# Board.net
KiCad netlist of a schematic drawn in EAGLE
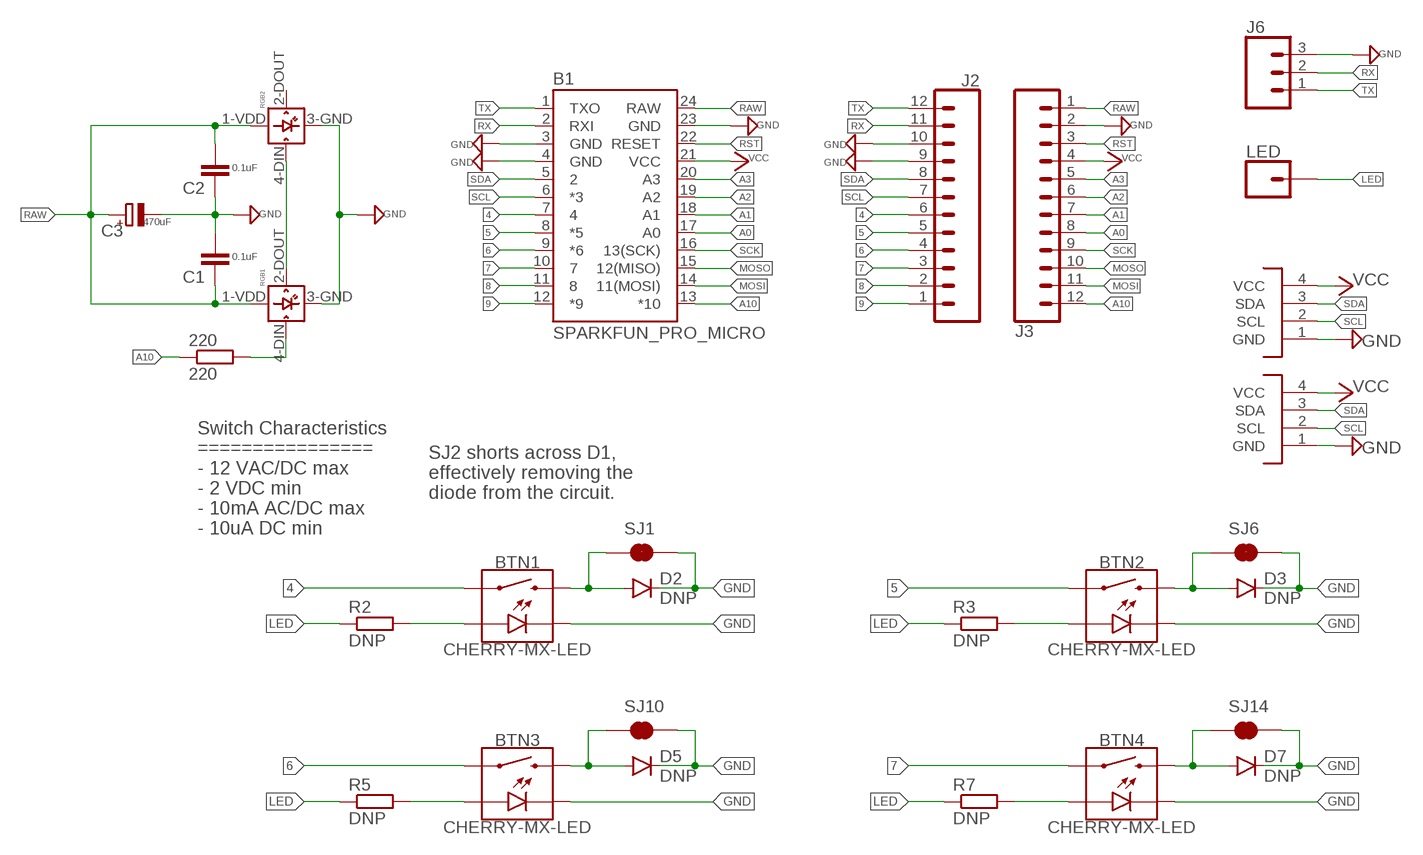
[diagram p0: schematic, sheet 1]

(export (version "E")
  (design (tool "Eeschema 10.0.6"))
  (components
    (comp (ref "220")
      (value "220")
      (footprint "eagle-import:0207_10")
      (libsource (lib "eagle-import") (part "resistor_348_R-EU_0207/10"))
    )
    (comp (ref "B1")
      (value "SPARKFUN_PRO_MICRO")
      (footprint "eagle-import:SPARKFUN_PRO_MICRO")
      (libsource (lib "eagle-import") (part "SPARKFUN_PRO_MICRO"))
    )
    (comp (ref "BTN1")
      (value "CHERRY-MX-LED")
      (footprint "eagle-import:CHERRY-MX-LED")
      (libsource (lib "eagle-import") (part "CHERRY-MX-LED"))
    )
    (comp (ref "BTN2")
      (value "CHERRY-MX-LED")
      (footprint "eagle-import:CHERRY-MX-LED")
      (libsource (lib "eagle-import") (part "CHERRY-MX-LED"))
    )
    (comp (ref "BTN3")
      (value "CHERRY-MX-LED")
      (footprint "eagle-import:CHERRY-MX-LED")
      (libsource (lib "eagle-import") (part "CHERRY-MX-LED"))
    )
    (comp (ref "BTN4")
      (value "CHERRY-MX-LED")
      (footprint "eagle-import:CHERRY-MX-LED")
      (libsource (lib "eagle-import") (part "CHERRY-MX-LED"))
    )
    (comp (ref "C1")
      (value "0.1uF")
      (footprint "eagle-import:CAP-PTH-SMALL-KIT")
      (libsource (lib "eagle-import") (part "0.1UF-KIT-EZ-50V-20%"))
    )
    (comp (ref "C2")
      (value "0.1uF")
      (footprint "eagle-import:CAP-PTH-SMALL-KIT")
      (libsource (lib "eagle-import") (part "0.1UF-KIT-EZ-50V-20%"))
    )
    (comp (ref "C3")
      (value "470uF")
      (footprint "eagle-import:E3,5-8")
      (libsource (lib "eagle-import") (part "CPOL-EUE3.5-8"))
    )
    (comp (ref "D2")
      (value "DNP")
      (footprint "eagle-import:DIODE-PTH-0.1")
      (libsource (lib "eagle-import") (part "DIODEPTH-VERT-0.1"))
    )
    (comp (ref "D3")
      (value "DNP")
      (footprint "eagle-import:DIODE-PTH-0.1")
      (libsource (lib "eagle-import") (part "DIODEPTH-VERT-0.1"))
    )
    (comp (ref "D5")
      (value "DNP")
      (footprint "eagle-import:DIODE-PTH-0.1")
      (libsource (lib "eagle-import") (part "DIODEPTH-VERT-0.1"))
    )
    (comp (ref "D7")
      (value "DNP")
      (footprint "eagle-import:DIODE-PTH-0.1")
      (libsource (lib "eagle-import") (part "DIODEPTH-VERT-0.1"))
    )
    (comp (ref "J2")
      (value "CONN_12")
      (footprint "eagle-import:1X12")
      (libsource (lib "eagle-import") (part "CONN_12"))
    )
    (comp (ref "J3")
      (value "CONN_12")
      (footprint "eagle-import:1X12")
      (libsource (lib "eagle-import") (part "CONN_12"))
    )
    (comp (ref "J4")
      (value "I2C-HEADER")
      (footprint "eagle-import:HEADER-4X1-2.54")
      (libsource (lib "eagle-import") (part "I2C-HEADER"))
    )
    (comp (ref "J5")
      (value "I2C-HEADER")
      (footprint "eagle-import:HEADER-4X1-2.54")
      (libsource (lib "eagle-import") (part "I2C-HEADER"))
    )
    (comp (ref "J6")
      (value "CONN_03")
      (footprint "eagle-import:1X03")
      (libsource (lib "eagle-import") (part "CONN_03"))
    )
    (comp (ref "LED")
      (value "CONN_01")
      (footprint "eagle-import:1X01")
      (libsource (lib "eagle-import") (part "CONN_01"))
    )
    (comp (ref "R2")
      (value "DNP")
      (footprint "eagle-import:0207_10")
      (libsource (lib "eagle-import") (part "R-EU_0207/10"))
    )
    (comp (ref "R3")
      (value "DNP")
      (footprint "eagle-import:0207_10")
      (libsource (lib "eagle-import") (part "R-EU_0207/10"))
    )
    (comp (ref "R5")
      (value "DNP")
      (footprint "eagle-import:0207_10")
      (libsource (lib "eagle-import") (part "R-EU_0207/10"))
    )
    (comp (ref "R7")
      (value "DNP")
      (footprint "eagle-import:0207_10")
      (libsource (lib "eagle-import") (part "R-EU_0207/10"))
    )
    (comp (ref "RGB1")
      (value "WS2812B")
      (footprint "eagle-import:WS2812B")
      (libsource (lib "eagle-import") (part "WS2812B"))
    )
    (comp (ref "RGB2")
      (value "WS2812B")
      (footprint "eagle-import:WS2812B")
      (libsource (lib "eagle-import") (part "WS2812B"))
    )
    (comp (ref "SJ1")
      (value "JUMPER-PAD-2-NC_BY_TRACENO_SILK")
      (footprint "eagle-import:PAD-JUMPER-2-NC_BY_TRACE_NO_SILK")
      (libsource (lib "eagle-import") (part "JUMPER-PAD-2-NC_BY_TRACENO_SILK"))
    )
    (comp (ref "SJ6")
      (value "JUMPER-PAD-2-NC_BY_TRACENO_SILK")
      (footprint "eagle-import:PAD-JUMPER-2-NC_BY_TRACE_NO_SILK")
      (libsource (lib "eagle-import") (part "JUMPER-PAD-2-NC_BY_TRACENO_SILK"))
    )
    (comp (ref "SJ10")
      (value "JUMPER-PAD-2-NC_BY_TRACENO_SILK")
      (footprint "eagle-import:PAD-JUMPER-2-NC_BY_TRACE_NO_SILK")
      (libsource (lib "eagle-import") (part "JUMPER-PAD-2-NC_BY_TRACENO_SILK"))
    )
    (comp (ref "SJ14")
      (value "JUMPER-PAD-2-NC_BY_TRACENO_SILK")
      (footprint "eagle-import:PAD-JUMPER-2-NC_BY_TRACE_NO_SILK")
      (libsource (lib "eagle-import") (part "JUMPER-PAD-2-NC_BY_TRACENO_SILK"))
    )
  )
  (nets
    (net (code "1") (name "4") (class "Default")
      (node (ref "B1") (pin "7") (pinfunction "4_7") (pintype "bidirectional"))
      (node (ref "BTN1") (pin "S1") (pinfunction "S1_S1") (pintype "passive"))
      (node (ref "J2") (pin "6") (pinfunction "6_6") (pintype "passive"))
    )
    (net (code "2") (name "5") (class "Default")
      (node (ref "B1") (pin "8") (pinfunction "*5_8") (pintype "bidirectional"))
      (node (ref "BTN2") (pin "S1") (pinfunction "S1_S1") (pintype "passive"))
      (node (ref "J2") (pin "5") (pinfunction "5_5") (pintype "passive"))
    )
    (net (code "3") (name "6") (class "Default")
      (node (ref "B1") (pin "9") (pinfunction "*6_9") (pintype "bidirectional"))
      (node (ref "BTN3") (pin "S1") (pinfunction "S1_S1") (pintype "passive"))
      (node (ref "J2") (pin "4") (pinfunction "4_4") (pintype "passive"))
    )
    (net (code "4") (name "7") (class "Default")
      (node (ref "B1") (pin "10") (pinfunction "7_10") (pintype "bidirectional"))
      (node (ref "BTN4") (pin "S1") (pinfunction "S1_S1") (pintype "passive"))
      (node (ref "J2") (pin "3") (pinfunction "3_3") (pintype "passive"))
    )
    (net (code "5") (name "8") (class "Default")
      (node (ref "B1") (pin "11") (pinfunction "8_11") (pintype "bidirectional"))
      (node (ref "J2") (pin "2") (pinfunction "2_2") (pintype "passive"))
    )
    (net (code "6") (name "9") (class "Default")
      (node (ref "B1") (pin "12") (pinfunction "*9_12") (pintype "bidirectional"))
      (node (ref "J2") (pin "1") (pinfunction "1_1") (pintype "passive"))
    )
    (net (code "7") (name "A0") (class "Default")
      (node (ref "B1") (pin "17") (pinfunction "A0_17") (pintype "bidirectional"))
      (node (ref "J3") (pin "8") (pinfunction "8_8") (pintype "passive"))
    )
    (net (code "8") (name "A1") (class "Default")
      (node (ref "B1") (pin "18") (pinfunction "A1_18") (pintype "bidirectional"))
      (node (ref "J3") (pin "7") (pinfunction "7_7") (pintype "passive"))
    )
    (net (code "9") (name "A2") (class "Default")
      (node (ref "B1") (pin "19") (pinfunction "A2_19") (pintype "bidirectional"))
      (node (ref "J3") (pin "6") (pinfunction "6_6") (pintype "passive"))
    )
    (net (code "10") (name "A3") (class "Default")
      (node (ref "B1") (pin "20") (pinfunction "A3_20") (pintype "bidirectional"))
      (node (ref "J3") (pin "5") (pinfunction "5_5") (pintype "passive"))
    )
    (net (code "11") (name "A10") (class "Default")
      (node (ref "220") (pin "1") (pinfunction "1_1") (pintype "passive"))
      (node (ref "B1") (pin "13") (pinfunction "*10_13") (pintype "bidirectional"))
      (node (ref "J3") (pin "12") (pinfunction "12_12") (pintype "passive"))
    )
    (net (code "12") (name "GND") (class "Default")
      (node (ref "B1") (pin "23") (pinfunction "GND_23") (pintype "power_in"))
      (node (ref "B1") (pin "3") (pinfunction "GND_3") (pintype "power_in"))
      (node (ref "B1") (pin "4") (pinfunction "GND_4") (pintype "power_in"))
      (node (ref "BTN1") (pin "K") (pinfunction "C_K") (pintype "passive"))
      (node (ref "BTN2") (pin "K") (pinfunction "C_K") (pintype "passive"))
      (node (ref "BTN3") (pin "K") (pinfunction "C_K") (pintype "passive"))
      (node (ref "BTN4") (pin "K") (pinfunction "C_K") (pintype "passive"))
      (node (ref "C1") (pin "2") (pinfunction "2_2") (pintype "passive"))
      (node (ref "C2") (pin "1") (pinfunction "1_1") (pintype "passive"))
      (node (ref "C3") (pin "-") (pinfunction "-_-") (pintype "passive"))
      (node (ref "D2") (pin "C") (pinfunction "C_C") (pintype "passive"))
      (node (ref "D3") (pin "C") (pinfunction "C_C") (pintype "passive"))
      (node (ref "D5") (pin "C") (pinfunction "C_C") (pintype "passive"))
      (node (ref "D7") (pin "C") (pinfunction "C_C") (pintype "passive"))
      (node (ref "J2") (pin "10") (pinfunction "10_10") (pintype "passive"))
      (node (ref "J2") (pin "9") (pinfunction "9_9") (pintype "passive"))
      (node (ref "J3") (pin "2") (pinfunction "2_2") (pintype "passive"))
      (node (ref "J4") (pin "1") (pinfunction "GND_1") (pintype "bidirectional"))
      (node (ref "J5") (pin "1") (pinfunction "GND_1") (pintype "bidirectional"))
      (node (ref "J6") (pin "3") (pinfunction "3_3") (pintype "passive"))
      (node (ref "RGB1") (pin "3-GND") (pinfunction "GND_3-GND") (pintype "bidirectional"))
      (node (ref "RGB2") (pin "3-GND") (pinfunction "GND_3-GND") (pintype "bidirectional"))
      (node (ref "SJ1") (pin "2") (pinfunction "2_2") (pintype "passive"))
      (node (ref "SJ10") (pin "2") (pinfunction "2_2") (pintype "passive"))
      (node (ref "SJ14") (pin "2") (pinfunction "2_2") (pintype "passive"))
      (node (ref "SJ6") (pin "2") (pinfunction "2_2") (pintype "passive"))
    )
    (net (code "13") (name "LED") (class "Default")
      (node (ref "LED") (pin "1") (pinfunction "1_1") (pintype "passive"))
      (node (ref "R2") (pin "1") (pinfunction "1_1") (pintype "passive"))
      (node (ref "R3") (pin "1") (pinfunction "1_1") (pintype "passive"))
      (node (ref "R5") (pin "1") (pinfunction "1_1") (pintype "passive"))
      (node (ref "R7") (pin "1") (pinfunction "1_1") (pintype "passive"))
    )
    (net (code "14") (name "MOSI") (class "Default")
      (node (ref "B1") (pin "14") (pinfunction "11(MOSI)_14") (pintype "bidirectional"))
      (node (ref "J3") (pin "11") (pinfunction "11_11") (pintype "passive"))
    )
    (net (code "15") (name "MOSO") (class "Default")
      (node (ref "B1") (pin "15") (pinfunction "12(MISO)_15") (pintype "bidirectional"))
      (node (ref "J3") (pin "10") (pinfunction "10_10") (pintype "passive"))
    )
    (net (code "16") (name "Net-(BTN1-PadA)") (class "Default")
      (node (ref "BTN1") (pin "A") (pinfunction "A_A") (pintype "passive"))
      (node (ref "R2") (pin "2") (pinfunction "2_2") (pintype "passive"))
    )
    (net (code "17") (name "Net-(BTN1-PadS2)") (class "Default")
      (node (ref "BTN1") (pin "S2") (pinfunction "S2_S2") (pintype "passive"))
      (node (ref "D2") (pin "A") (pinfunction "A_A") (pintype "passive"))
      (node (ref "SJ1") (pin "1") (pinfunction "1_1") (pintype "passive"))
    )
    (net (code "18") (name "Net-(BTN2-PadA)") (class "Default")
      (node (ref "BTN2") (pin "A") (pinfunction "A_A") (pintype "passive"))
      (node (ref "R3") (pin "2") (pinfunction "2_2") (pintype "passive"))
    )
    (net (code "19") (name "Net-(BTN2-PadS2)") (class "Default")
      (node (ref "BTN2") (pin "S2") (pinfunction "S2_S2") (pintype "passive"))
      (node (ref "D3") (pin "A") (pinfunction "A_A") (pintype "passive"))
      (node (ref "SJ6") (pin "1") (pinfunction "1_1") (pintype "passive"))
    )
    (net (code "20") (name "Net-(BTN3-PadA)") (class "Default")
      (node (ref "BTN3") (pin "A") (pinfunction "A_A") (pintype "passive"))
      (node (ref "R5") (pin "2") (pinfunction "2_2") (pintype "passive"))
    )
    (net (code "21") (name "Net-(BTN3-PadS2)") (class "Default")
      (node (ref "BTN3") (pin "S2") (pinfunction "S2_S2") (pintype "passive"))
      (node (ref "D5") (pin "A") (pinfunction "A_A") (pintype "passive"))
      (node (ref "SJ10") (pin "1") (pinfunction "1_1") (pintype "passive"))
    )
    (net (code "22") (name "Net-(BTN4-PadA)") (class "Default")
      (node (ref "BTN4") (pin "A") (pinfunction "A_A") (pintype "passive"))
      (node (ref "R7") (pin "2") (pinfunction "2_2") (pintype "passive"))
    )
    (net (code "23") (name "Net-(BTN4-PadS2)") (class "Default")
      (node (ref "BTN4") (pin "S2") (pinfunction "S2_S2") (pintype "passive"))
      (node (ref "D7") (pin "A") (pinfunction "A_A") (pintype "passive"))
      (node (ref "SJ14") (pin "1") (pinfunction "1_1") (pintype "passive"))
    )
    (net (code "24") (name "Net-(RGB1-DIN)") (class "Default")
      (node (ref "220") (pin "2") (pinfunction "2_2") (pintype "passive"))
      (node (ref "RGB1") (pin "4-DIN") (pinfunction "DIN_4-DIN") (pintype "input"))
    )
    (net (code "25") (name "Net-(RGB1-DOUT)") (class "Default")
      (node (ref "RGB1") (pin "2-DOUT") (pinfunction "DOUT_2-DOUT") (pintype "output"))
      (node (ref "RGB2") (pin "4-DIN") (pinfunction "DIN_4-DIN") (pintype "input"))
    )
    (net (code "26") (name "RAW") (class "Default")
      (node (ref "B1") (pin "24") (pinfunction "RAW_24") (pintype "power_in"))
      (node (ref "C1") (pin "1") (pinfunction "1_1") (pintype "passive"))
      (node (ref "C2") (pin "2") (pinfunction "2_2") (pintype "passive"))
      (node (ref "C3") (pin "+") (pinfunction "+_+") (pintype "passive"))
      (node (ref "J3") (pin "1") (pinfunction "1_1") (pintype "passive"))
      (node (ref "RGB1") (pin "1-VDD") (pinfunction "VDD_1-VDD") (pintype "bidirectional"))
      (node (ref "RGB2") (pin "1-VDD") (pinfunction "VDD_1-VDD") (pintype "bidirectional"))
    )
    (net (code "27") (name "RST") (class "Default")
      (node (ref "B1") (pin "22") (pinfunction "RESET_22") (pintype "bidirectional"))
      (node (ref "J3") (pin "3") (pinfunction "3_3") (pintype "passive"))
    )
    (net (code "28") (name "RX") (class "Default")
      (node (ref "B1") (pin "2") (pinfunction "RXI_2") (pintype "bidirectional"))
      (node (ref "J2") (pin "11") (pinfunction "11_11") (pintype "passive"))
      (node (ref "J6") (pin "2") (pinfunction "2_2") (pintype "passive"))
    )
    (net (code "29") (name "SCK") (class "Default")
      (node (ref "B1") (pin "16") (pinfunction "13(SCK)_16") (pintype "bidirectional"))
      (node (ref "J3") (pin "9") (pinfunction "9_9") (pintype "passive"))
    )
    (net (code "30") (name "SCL") (class "Default")
      (node (ref "B1") (pin "6") (pinfunction "*3_6") (pintype "bidirectional"))
      (node (ref "J2") (pin "7") (pinfunction "7_7") (pintype "passive"))
      (node (ref "J4") (pin "2") (pinfunction "SCL_2") (pintype "bidirectional"))
      (node (ref "J5") (pin "2") (pinfunction "SCL_2") (pintype "bidirectional"))
    )
    (net (code "31") (name "SDA") (class "Default")
      (node (ref "B1") (pin "5") (pinfunction "2_5") (pintype "bidirectional"))
      (node (ref "J2") (pin "8") (pinfunction "8_8") (pintype "passive"))
      (node (ref "J4") (pin "3") (pinfunction "SDA_3") (pintype "bidirectional"))
      (node (ref "J5") (pin "3") (pinfunction "SDA_3") (pintype "bidirectional"))
    )
    (net (code "32") (name "TX") (class "Default")
      (node (ref "B1") (pin "1") (pinfunction "TXO_1") (pintype "bidirectional"))
      (node (ref "J2") (pin "12") (pinfunction "12_12") (pintype "passive"))
      (node (ref "J6") (pin "1") (pinfunction "1_1") (pintype "passive"))
    )
    (net (code "33") (name "VCC") (class "Default")
      (node (ref "B1") (pin "21") (pinfunction "VCC_21") (pintype "power_in"))
      (node (ref "J3") (pin "4") (pinfunction "4_4") (pintype "passive"))
      (node (ref "J4") (pin "4") (pinfunction "VCC_4") (pintype "bidirectional"))
      (node (ref "J5") (pin "4") (pinfunction "VCC_4") (pintype "bidirectional"))
    )
    (net (code "34") (name "unconnected-(RGB2-DOUT-Pad2-DOUT)") (class "Default")
      (node (ref "RGB2") (pin "2-DOUT") (pinfunction "DOUT_2-DOUT") (pintype "output"))
    )
  )
)
